# Adafruit_ADS1015_ADC_STEMMA_QT.net
KiCad netlist of a schematic drawn in EAGLE
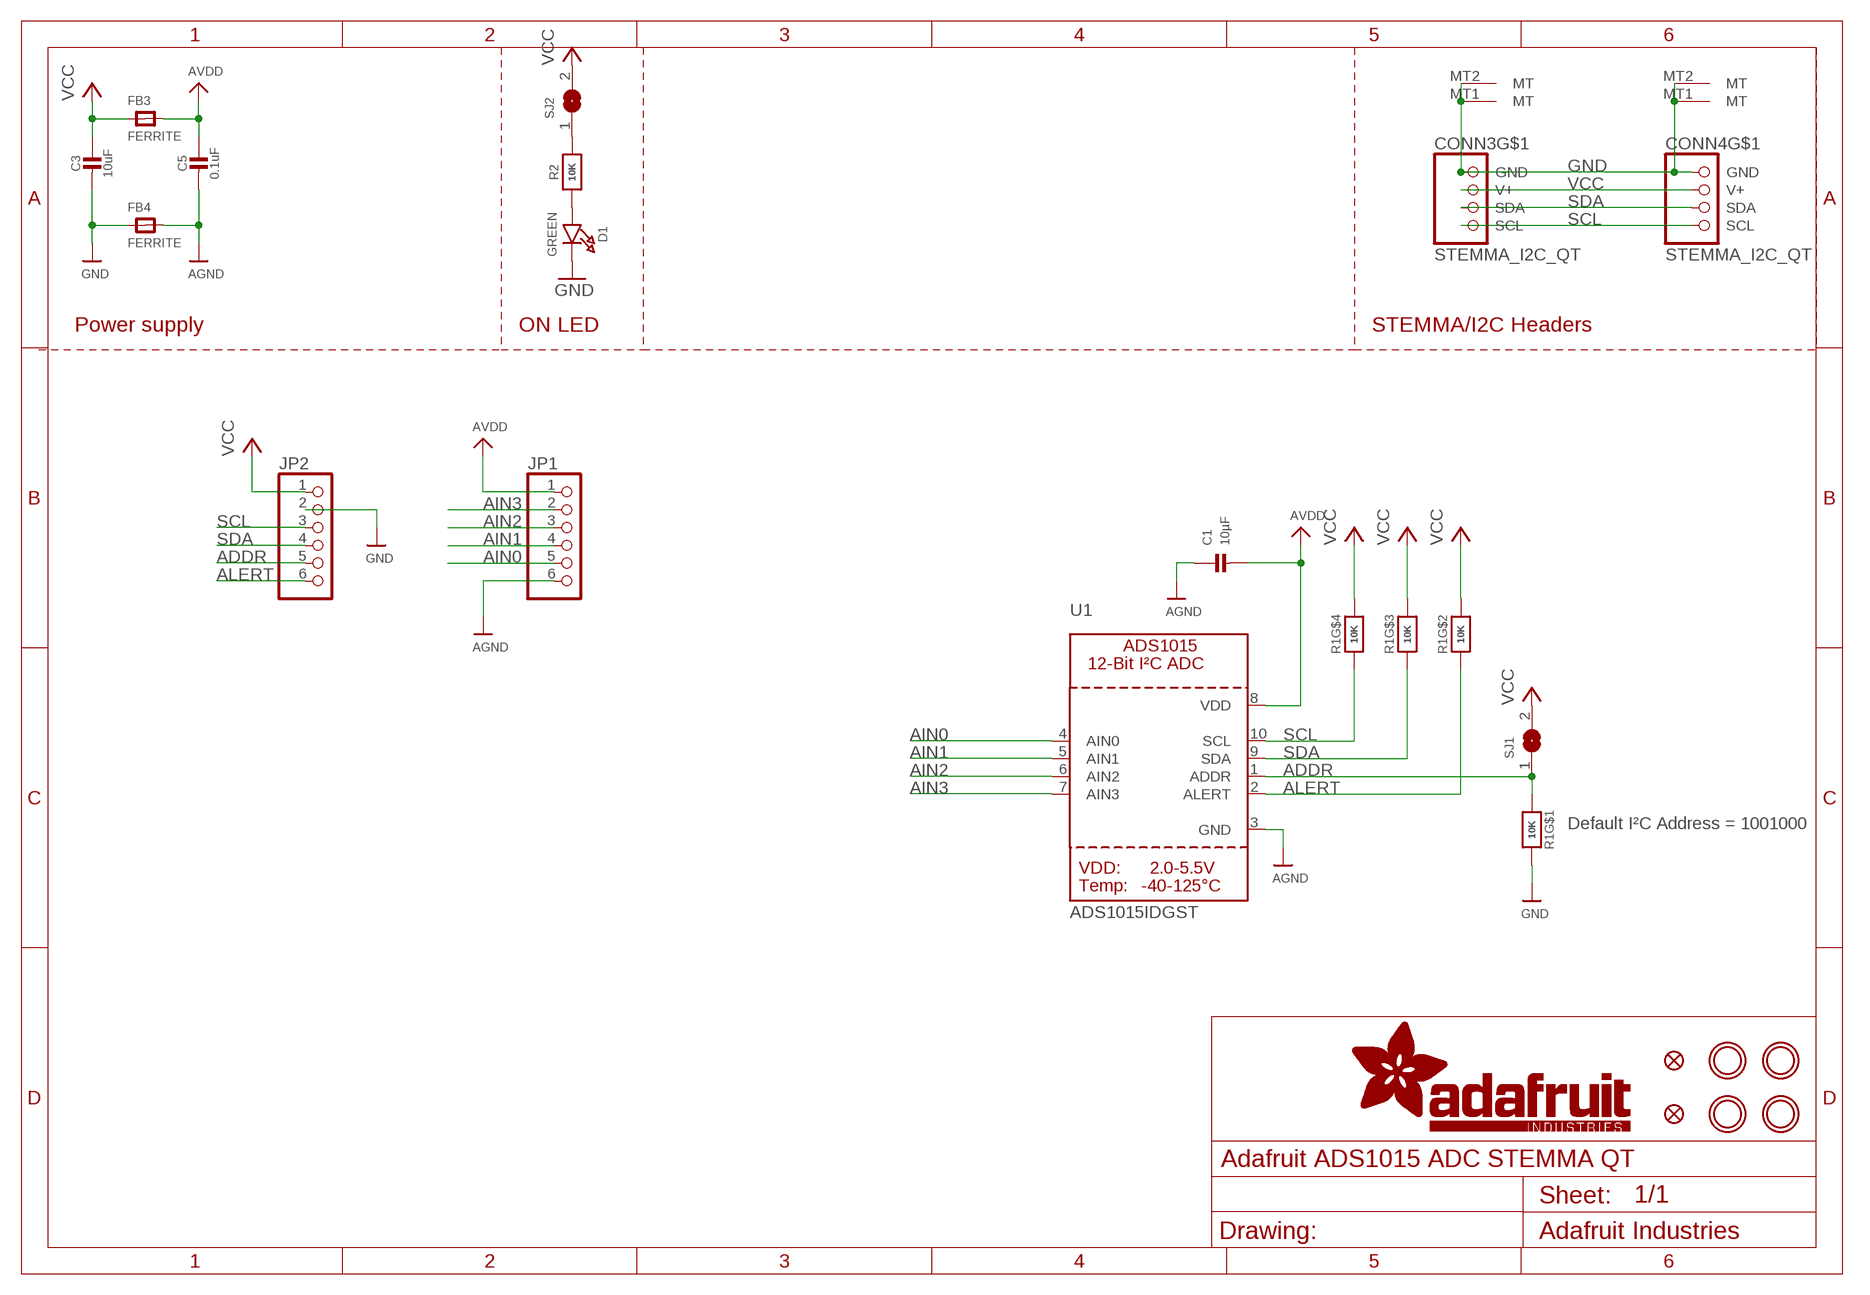
[diagram p0: schematic, sheet 1]

(export (version "E")
  (design (tool "Eeschema 10.0.6"))
  (components
    (comp (ref "C1")
      (value "10µF")
      (footprint "eagle-import:0805-NO")
      (libsource (lib "eagle-import") (part "CAP_CERAMIC0805-NOOUTLINE"))
    )
    (comp (ref "C3")
      (value "10uF")
      (footprint "eagle-import:0805-NO")
      (libsource (lib "eagle-import") (part "CAP_CERAMIC0805-NOOUTLINE"))
    )
    (comp (ref "C5")
      (value "0.1uF")
      (footprint "eagle-import:0603-NO")
      (libsource (lib "eagle-import") (part "CAP_CERAMIC0603_NO"))
    )
    (comp (ref "CONN3")
      (value "STEMMA_I2C_QT")
      (footprint "eagle-import:JST_SH4")
      (libsource (lib "eagle-import") (part "STEMMA_I2C_QT"))
    )
    (comp (ref "CONN4")
      (value "STEMMA_I2C_QT")
      (footprint "eagle-import:JST_SH4")
      (libsource (lib "eagle-import") (part "STEMMA_I2C_QT"))
    )
    (comp (ref "D1")
      (value "GREEN")
      (footprint "eagle-import:CHIPLED_0603_NOOUTLINE")
      (libsource (lib "eagle-import") (part "LED0603_NOOUTLINE"))
    )
    (comp (ref "FB3")
      (value "FERRITE")
      (footprint "eagle-import:0603-NO")
      (libsource (lib "eagle-import") (part "FERRITE-0603NO"))
    )
    (comp (ref "FB4")
      (value "FERRITE")
      (footprint "eagle-import:0603-NO")
      (libsource (lib "eagle-import") (part "FERRITE-0603NO"))
    )
    (comp (ref "FID3")
      (value "FIDUCIAL_1MM")
      (footprint "eagle-import:FIDUCIAL_1MM")
      (libsource (lib "eagle-import") (part "FIDUCIAL_1MM"))
    )
    (comp (ref "FID4")
      (value "FIDUCIAL_1MM")
      (footprint "eagle-import:FIDUCIAL_1MM")
      (libsource (lib "eagle-import") (part "FIDUCIAL_1MM"))
    )
    (comp (ref "JP1")
      (value "HEADER-1X670MIL")
      (footprint "eagle-import:1X06_ROUND_70")
      (libsource (lib "eagle-import") (part "HEADER-1X670MIL"))
    )
    (comp (ref "JP2")
      (value "HEADER-1X670MIL")
      (footprint "eagle-import:1X06_ROUND_70")
      (libsource (lib "eagle-import") (part "HEADER-1X670MIL"))
    )
    (comp (ref "R1")
      (value "10K")
      (footprint "eagle-import:RESPACK_4X0603")
      (libsource (lib "eagle-import") (part "RESISTOR_4PACK"))
    )
    (comp (ref "R2")
      (value "10K")
      (footprint "eagle-import:0603-NO")
      (libsource (lib "eagle-import") (part "RESISTOR_0603_NOOUT"))
    )
    (comp (ref "SJ1")
      (value "SOLDERJUMPER")
      (footprint "eagle-import:SOLDERJUMPER_ARROW_NOPASTE")
      (libsource (lib "eagle-import") (part "SOLDERJUMPER"))
    )
    (comp (ref "SJ2")
      (value "SOLDERJUMPERCLOSED")
      (footprint "eagle-import:SOLDERJUMPER_CLOSEDWIRE")
      (libsource (lib "eagle-import") (part "SOLDERJUMPERCLOSED"))
    )
    (comp (ref "U$25")
      (value "MOUNTINGHOLE2.5")
      (footprint "eagle-import:MOUNTINGHOLE_2.5_PLATED")
      (libsource (lib "eagle-import") (part "MOUNTINGHOLE2.5"))
    )
    (comp (ref "U$27")
      (value "MOUNTINGHOLE2.5")
      (footprint "eagle-import:MOUNTINGHOLE_2.5_PLATED")
      (libsource (lib "eagle-import") (part "MOUNTINGHOLE2.5"))
    )
    (comp (ref "U$29")
      (value "MOUNTINGHOLE2.5")
      (footprint "eagle-import:MOUNTINGHOLE_2.5_PLATED")
      (libsource (lib "eagle-import") (part "MOUNTINGHOLE2.5"))
    )
    (comp (ref "U$30")
      (value "MOUNTINGHOLE2.5")
      (footprint "eagle-import:MOUNTINGHOLE_2.5_PLATED")
      (libsource (lib "eagle-import") (part "MOUNTINGHOLE2.5"))
    )
    (comp (ref "U1")
      (value "ADS1015IDGST")
      (footprint "eagle-import:MSOP10")
      (libsource (lib "eagle-import") (part "ADC_ADS1015"))
    )
  )
  (nets
    (net (code "1") (name "/ADDR") (class "Default")
      (node (ref "JP2") (pin "5") (pinfunction "5_5") (pintype "passive"))
      (node (ref "R1") (pin "1") (pinfunction "1_1") (pintype "passive"))
      (node (ref "SJ1") (pin "1") (pinfunction "1_1") (pintype "passive"))
      (node (ref "U1") (pin "1") (pinfunction "ADDR_1") (pintype "bidirectional"))
    )
    (net (code "2") (name "/AIN0") (class "Default")
      (node (ref "JP1") (pin "5") (pinfunction "5_5") (pintype "passive"))
      (node (ref "U1") (pin "4") (pinfunction "AIN0_4") (pintype "bidirectional"))
    )
    (net (code "3") (name "/AIN1") (class "Default")
      (node (ref "JP1") (pin "4") (pinfunction "4_4") (pintype "passive"))
      (node (ref "U1") (pin "5") (pinfunction "AIN1_5") (pintype "bidirectional"))
    )
    (net (code "4") (name "/AIN2") (class "Default")
      (node (ref "JP1") (pin "3") (pinfunction "3_3") (pintype "passive"))
      (node (ref "U1") (pin "6") (pinfunction "AIN2_6") (pintype "bidirectional"))
    )
    (net (code "5") (name "/AIN3") (class "Default")
      (node (ref "JP1") (pin "2") (pinfunction "2_2") (pintype "passive"))
      (node (ref "U1") (pin "7") (pinfunction "AIN3_7") (pintype "bidirectional"))
    )
    (net (code "6") (name "/ALERT") (class "Default")
      (node (ref "JP2") (pin "6") (pinfunction "6_6") (pintype "passive"))
      (node (ref "R1") (pin "2") (pinfunction "1_2") (pintype "passive"))
      (node (ref "U1") (pin "2") (pinfunction "ALERT_2") (pintype "bidirectional"))
    )
    (net (code "7") (name "/SCL") (class "Default")
      (node (ref "CONN3") (pin "4") (pinfunction "SCL_4") (pintype "passive"))
      (node (ref "CONN4") (pin "4") (pinfunction "SCL_4") (pintype "passive"))
      (node (ref "JP2") (pin "3") (pinfunction "3_3") (pintype "passive"))
      (node (ref "R1") (pin "4") (pinfunction "1_4") (pintype "passive"))
      (node (ref "U1") (pin "10") (pinfunction "SCL_10") (pintype "bidirectional"))
    )
    (net (code "8") (name "/SDA") (class "Default")
      (node (ref "CONN3") (pin "3") (pinfunction "SDA_3") (pintype "passive"))
      (node (ref "CONN4") (pin "3") (pinfunction "SDA_3") (pintype "passive"))
      (node (ref "JP2") (pin "4") (pinfunction "4_4") (pintype "passive"))
      (node (ref "R1") (pin "3") (pinfunction "1_3") (pintype "passive"))
      (node (ref "U1") (pin "9") (pinfunction "SDA_9") (pintype "bidirectional"))
    )
    (net (code "9") (name "AGND") (class "Default")
      (node (ref "C1") (pin "1") (pinfunction "1_1") (pintype "passive"))
      (node (ref "C5") (pin "2") (pinfunction "2_2") (pintype "passive"))
      (node (ref "FB4") (pin "2") (pinfunction "P$2_2") (pintype "passive"))
      (node (ref "JP1") (pin "6") (pinfunction "6_6") (pintype "passive"))
      (node (ref "U1") (pin "3") (pinfunction "GND_3") (pintype "bidirectional"))
    )
    (net (code "10") (name "AVDD") (class "Default")
      (node (ref "C1") (pin "2") (pinfunction "2_2") (pintype "passive"))
      (node (ref "C5") (pin "1") (pinfunction "1_1") (pintype "passive"))
      (node (ref "FB3") (pin "2") (pinfunction "P$2_2") (pintype "passive"))
      (node (ref "JP1") (pin "1") (pinfunction "1_1") (pintype "passive"))
      (node (ref "U1") (pin "8") (pinfunction "VDD_8") (pintype "bidirectional"))
    )
    (net (code "11") (name "GND") (class "Default")
      (node (ref "C3") (pin "2") (pinfunction "2_2") (pintype "passive"))
      (node (ref "CONN3") (pin "1") (pinfunction "GND_1") (pintype "passive"))
      (node (ref "CONN3") (pin "MT1") (pinfunction "MT_MT1") (pintype "bidirectional"))
      (node (ref "CONN3") (pin "MT2") (pinfunction "MT_MT2") (pintype "bidirectional"))
      (node (ref "CONN4") (pin "1") (pinfunction "GND_1") (pintype "passive"))
      (node (ref "CONN4") (pin "MT1") (pinfunction "MT_MT1") (pintype "bidirectional"))
      (node (ref "CONN4") (pin "MT2") (pinfunction "MT_MT2") (pintype "bidirectional"))
      (node (ref "D1") (pin "C") (pinfunction "C_C") (pintype "passive"))
      (node (ref "FB4") (pin "1") (pinfunction "P$1_1") (pintype "passive"))
      (node (ref "JP2") (pin "2") (pinfunction "2_2") (pintype "passive"))
      (node (ref "R1") (pin "8") (pinfunction "2_8") (pintype "passive"))
    )
    (net (code "12") (name "Net-(D1-PadA)") (class "Default")
      (node (ref "D1") (pin "A") (pinfunction "A_A") (pintype "passive"))
      (node (ref "R2") (pin "1") (pinfunction "1_1") (pintype "passive"))
    )
    (net (code "13") (name "Net-(R2-Pad2)") (class "Default")
      (node (ref "R2") (pin "2") (pinfunction "2_2") (pintype "passive"))
      (node (ref "SJ2") (pin "1") (pinfunction "1_1") (pintype "passive"))
    )
    (net (code "14") (name "VCC") (class "Default")
      (node (ref "C3") (pin "1") (pinfunction "1_1") (pintype "passive"))
      (node (ref "CONN3") (pin "2") (pinfunction "V+_2") (pintype "passive"))
      (node (ref "CONN4") (pin "2") (pinfunction "V+_2") (pintype "passive"))
      (node (ref "FB3") (pin "1") (pinfunction "P$1_1") (pintype "passive"))
      (node (ref "JP2") (pin "1") (pinfunction "1_1") (pintype "passive"))
      (node (ref "R1") (pin "5") (pinfunction "2_5") (pintype "passive"))
      (node (ref "R1") (pin "6") (pinfunction "2_6") (pintype "passive"))
      (node (ref "R1") (pin "7") (pinfunction "2_7") (pintype "passive"))
      (node (ref "SJ1") (pin "2") (pinfunction "2_2") (pintype "passive"))
      (node (ref "SJ2") (pin "2") (pinfunction "2_2") (pintype "passive"))
    )
  )
)
